# 7_High_Voltage.net
KiCad netlist of a schematic drawn in Altium Designer
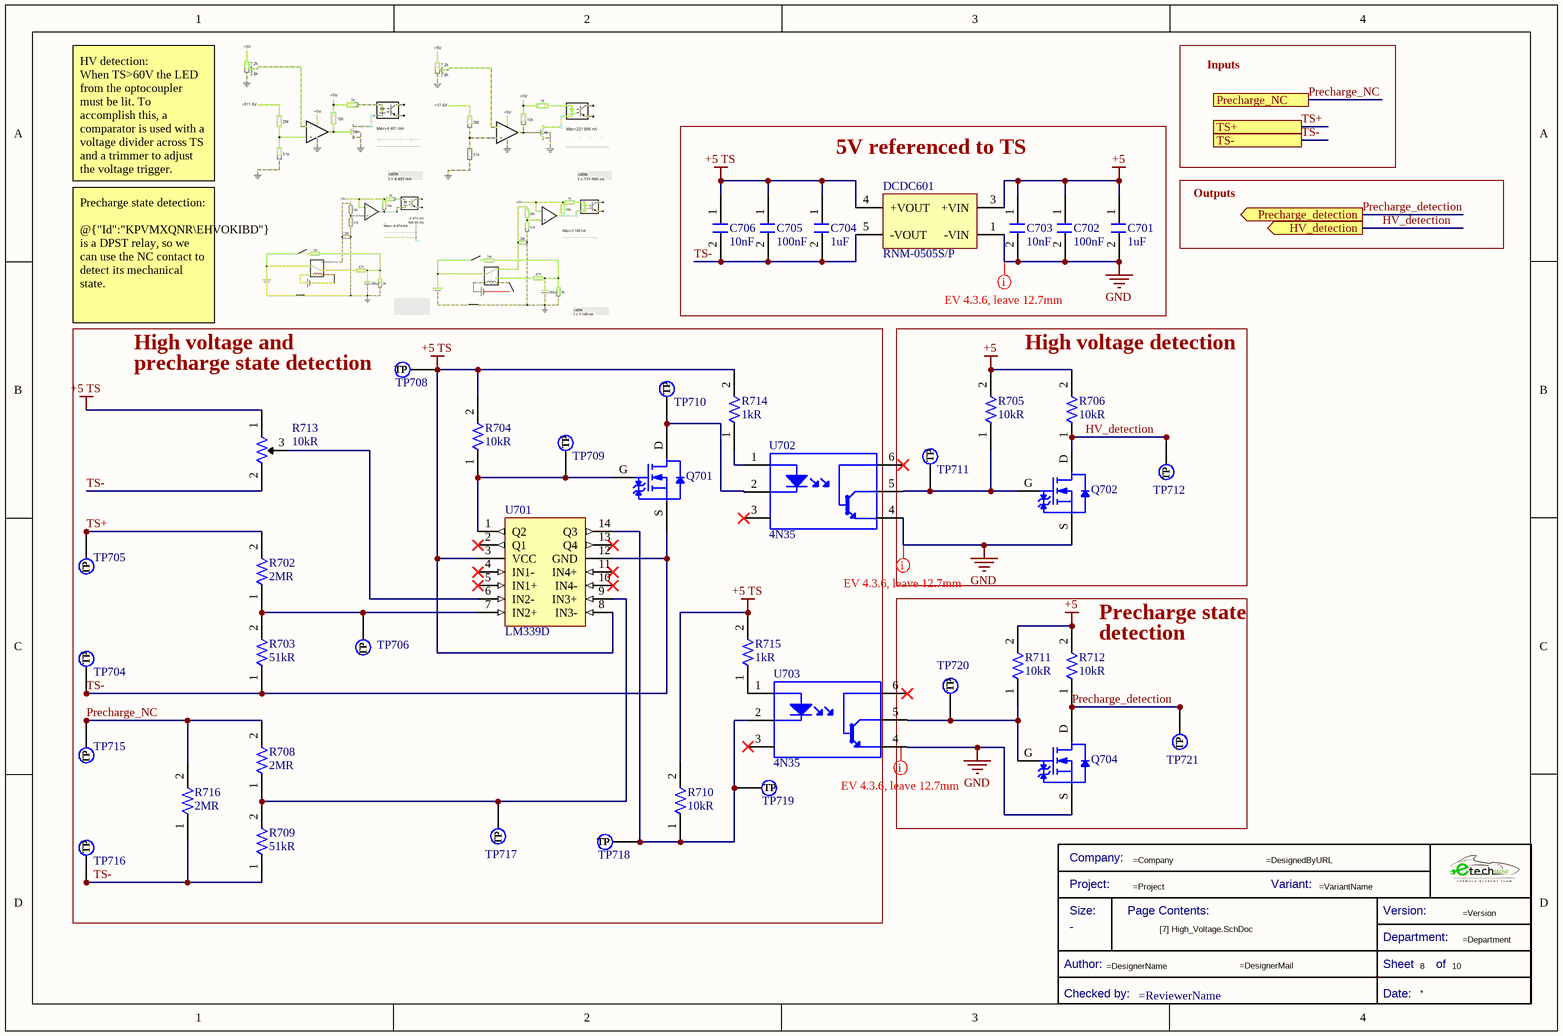
[diagram p0: [7] High_Voltage.SchDoc]

(export (version "E")
  (design (tool "Eeschema 10.0.6"))
  (components
    (comp (ref "*")
      (value "Title Block_template")
      (description "Standard Title Block")
      (fields (field (name "SIZE") "-"))
      (libsource (lib "e-Tech_Racing") (part "Title Block_template"))
    )
    (comp (ref "C701")
      (value "885012207103")
      (footprint "C0805FNPC-R")
      (fields
        (field (name "TOLERANCE") "10%")
        (field (name "CAPACITANCE") "1uF")
        (field (name ".CREATOR") "GP")
      )
      (libsource (lib "Passives") (part "C1u-50V-0805FNPC-X7R"))
    )
    (comp (ref "C702")
      (value "885012207098")
      (footprint "C0805FNPC-R")
      (description "Cap, 0.1ΜF, 50V, 10%, X7R, 0805")
      (fields
        (field (name "TOLERANCE") "10%")
        (field (name "CAPACITANCE") "100nF")
        (field (name ".CREATOR") "DR")
      )
      (libsource (lib "Passives") (part "C100n-50V-0805FNPC-X7R"))
    )
    (comp (ref "C703")
      (value "885012207092")
      (footprint "C0805FNPC-R")
      (description "Cap, 0.01ΜF, 50V, 10%, X7R, 0805")
      (fields
        (field (name "TOLERANCE") "10%")
        (field (name "CAPACITANCE") "10nF")
        (field (name ".CREATOR") "DR")
      )
      (libsource (lib "Passives") (part "C10n-50V-0805FNPC-X7R"))
    )
    (comp (ref "C704")
      (value "885012207103")
      (footprint "C0805FNPC-R")
      (fields
        (field (name "TOLERANCE") "10%")
        (field (name "CAPACITANCE") "1uF")
        (field (name ".CREATOR") "GP")
      )
      (libsource (lib "Passives") (part "C1u-50V-0805FNPC-X7R"))
    )
    (comp (ref "C705")
      (value "885012207098")
      (footprint "C0805FNPC-R")
      (description "Cap, 0.1ΜF, 50V, 10%, X7R, 0805")
      (fields
        (field (name "TOLERANCE") "10%")
        (field (name "CAPACITANCE") "100nF")
        (field (name ".CREATOR") "DR")
      )
      (libsource (lib "Passives") (part "C100n-50V-0805FNPC-X7R"))
    )
    (comp (ref "C706")
      (value "885012207092")
      (footprint "C0805FNPC-R")
      (description "Cap, 0.01ΜF, 50V, 10%, X7R, 0805")
      (fields
        (field (name "TOLERANCE") "10%")
        (field (name "CAPACITANCE") "10nF")
        (field (name ".CREATOR") "DR")
      )
      (libsource (lib "Passives") (part "C10n-50V-0805FNPC-X7R"))
    )
    (comp (ref "DCDC601")
      (value "RNM-0505S/P")
      (footprint "DCDC_RNM-0505S/P")
      (description "1W DC/DC-Converter 'ECONOLINE' DIP6 1kV unreg; V. In: 05; V. Out: 05; mA. Out: 200")
      (fields
        (field (name "MANUFACTURER") "Recom")
        (field (name "MANUFACTURER PART NUMBER") "RNM-0505S/P")
        (field (name ".CREATOR") "GP")
      )
      (libsource (lib "Semiconductor") (part "DCDC_RNM-0505S/P"))
    )
    (comp (ref "Q701")
      (value "SQ2318BES-T1_GE3")
      (footprint "TRT-NCH-3/35-CPH")
      (description "Automotive N-channel 40 V (d-s) 175C Mosfet SOT-23")
      (fields (field (name ".CREATOR") "DO"))
      (libsource (lib "Semiconductor") (part "TRT-NCH-8/40-SQ"))
    )
    (comp (ref "Q702")
      (value "SQ2318BES-T1_GE3")
      (footprint "TRT-NCH-3/35-CPH")
      (description "Automotive N-channel 40 V (d-s) 175C Mosfet SOT-23")
      (fields (field (name ".CREATOR") "DO"))
      (libsource (lib "Semiconductor") (part "TRT-NCH-8/40-SQ"))
    )
    (comp (ref "Q704")
      (value "SQ2318BES-T1_GE3")
      (footprint "TRT-NCH-3/35-CPH")
      (description "Automotive N-channel 40 V (d-s) 175C Mosfet SOT-23")
      (fields (field (name ".CREATOR") "DO"))
      (libsource (lib "Semiconductor") (part "TRT-NCH-8/40-SQ"))
    )
    (comp (ref "R702")
      (value "R2M-2512FTK")
      (footprint "R2512FTK")
      (description "Current Sense Resistors - SMD 3watts .002ohms 1%")
      (fields
        (field (name "MANUFACTURER") "Vishay Dale")
        (field (name "MANUFACTURER PART NUMBER") "WSLP25122L000FEA")
        (field (name "RESISTANCE") "2MR")
      )
      (libsource (lib "Passives") (part "R2M-2512FTK"))
    )
    (comp (ref "R703")
      (value "CRCW120610K0FKEA")
      (footprint "R1206FTK-W")
      (description "Res Thick Film 1206 51K Ohm 1% 1/4W ±100ppm/°C Molded SMD SMD Punched Carrier T/R")
      (fields
        (field (name "MANUFACTURER") "Panasonic")
        (field (name "MANUFACTURER PART NUMBER") "ERJ-S08F5102V")
        (field (name "RESISTANCE") "51kR")
        (field (name ".CREATOR") "DO")
      )
      (libsource (lib "Passives") (part "R51k-1206FTK"))
    )
    (comp (ref "R704")
      (value "CR0805-JW-103ELF")
      (footprint "R0805FTK")
      (fields
        (field (name "TOLERANCE") "5%")
        (field (name "RESISTANCE") "10kR")
        (field (name ".CREATOR") "DR")
      )
      (libsource (lib "Passives") (part "R10k-0805FTK"))
    )
    (comp (ref "R705")
      (value "CR0805-JW-103ELF")
      (footprint "R0805FTK")
      (fields
        (field (name "TOLERANCE") "5%")
        (field (name "RESISTANCE") "10kR")
        (field (name ".CREATOR") "DR")
      )
      (libsource (lib "Passives") (part "R10k-0805FTK"))
    )
    (comp (ref "R706")
      (value "CR0805-JW-103ELF")
      (footprint "R0805FTK")
      (fields
        (field (name "TOLERANCE") "5%")
        (field (name "RESISTANCE") "10kR")
        (field (name ".CREATOR") "DR")
      )
      (libsource (lib "Passives") (part "R10k-0805FTK"))
    )
    (comp (ref "R708")
      (value "R2M-2512FTK")
      (footprint "R2512FTK")
      (description "Current Sense Resistors - SMD 3watts .002ohms 1%")
      (fields
        (field (name "MANUFACTURER") "Vishay Dale")
        (field (name "MANUFACTURER PART NUMBER") "WSLP25122L000FEA")
        (field (name "RESISTANCE") "2MR")
      )
      (libsource (lib "Passives") (part "R2M-2512FTK"))
    )
    (comp (ref "R709")
      (value "CRCW120610K0FKEA")
      (footprint "R1206FTK-W")
      (description "Res Thick Film 1206 51K Ohm 1% 1/4W ±100ppm/°C Molded SMD SMD Punched Carrier T/R")
      (fields
        (field (name "MANUFACTURER") "Panasonic")
        (field (name "MANUFACTURER PART NUMBER") "ERJ-S08F5102V")
        (field (name "RESISTANCE") "51kR")
        (field (name ".CREATOR") "DO")
      )
      (libsource (lib "Passives") (part "R51k-1206FTK"))
    )
    (comp (ref "R710")
      (value "CR0805-JW-103ELF")
      (footprint "R0805FTK")
      (fields
        (field (name "TOLERANCE") "5%")
        (field (name "RESISTANCE") "10kR")
        (field (name ".CREATOR") "DR")
      )
      (libsource (lib "Passives") (part "R10k-0805FTK"))
    )
    (comp (ref "R711")
      (value "CR0805-JW-103ELF")
      (footprint "R0805FTK")
      (fields
        (field (name "TOLERANCE") "5%")
        (field (name "RESISTANCE") "10kR")
        (field (name ".CREATOR") "DR")
      )
      (libsource (lib "Passives") (part "R10k-0805FTK"))
    )
    (comp (ref "R712")
      (value "CR0805-JW-103ELF")
      (footprint "R0805FTK")
      (fields
        (field (name "TOLERANCE") "5%")
        (field (name "RESISTANCE") "10kR")
        (field (name ".CREATOR") "DR")
      )
      (libsource (lib "Passives") (part "R10k-0805FTK"))
    )
    (comp (ref "R713")
      (value "3296W-1-103LF")
      (footprint "R10k-VTR")
      (description "Trimmer, Cermet, Rest 10 Kilohms, PCB, 25 Turns, Pwr-Rtg 0.5W, 3296 Series")
      (fields
        (field (name "MANUFACTURER") "Bourns")
        (field (name "TOLERANCE") "10%")
        (field (name "RESISTANCE") "10kR")
        (field (name ".CREATOR") "DO")
      )
      (libsource (lib "Passives") (part "R10k-VTR"))
    )
    (comp (ref "R714")
      (value "CR0805-JW-102ELF")
      (footprint "R0805FTK")
      (description "Res Thick Film 0805 1K Ohm 5% 1/8W ±200ppm/°C Molded SMD SMD Paper Tape on Plastic Reel")
      (fields
        (field (name "TOLERANCE") "5%")
        (field (name "RESISTANCE") "1kR")
        (field (name ".CREATOR") "GP")
      )
      (libsource (lib "Passives") (part "R1k-0805FTK"))
    )
    (comp (ref "R715")
      (value "CR0805-JW-102ELF")
      (footprint "R0805FTK")
      (description "Res Thick Film 0805 1K Ohm 5% 1/8W ±200ppm/°C Molded SMD SMD Paper Tape on Plastic Reel")
      (fields
        (field (name "TOLERANCE") "5%")
        (field (name "RESISTANCE") "1kR")
        (field (name ".CREATOR") "GP")
      )
      (libsource (lib "Passives") (part "R1k-0805FTK"))
    )
    (comp (ref "R716")
      (value "R2M-2512FTK")
      (footprint "R2512FTK")
      (description "Current Sense Resistors - SMD 3watts .002ohms 1%")
      (fields
        (field (name "MANUFACTURER") "Vishay Dale")
        (field (name "MANUFACTURER PART NUMBER") "WSLP25122L000FEA")
        (field (name "RESISTANCE") "2MR")
      )
      (libsource (lib "Passives") (part "R2M-2512FTK"))
    )
    (comp (ref "TP704")
      (value "TestPoint")
      (footprint "TestPoint")
      (description "Test Point 1x1 mm")
      (fields (field (name ".CREATOR") "GP") (field (name ".PCBCHECK") "GP") (field (name ".SCHCHECK") "GP"))
      (libsource (lib "e-Tech_Racing") (part "TestPoint"))
    )
    (comp (ref "TP705")
      (value "TestPoint")
      (footprint "TestPoint")
      (description "Test Point 1x1 mm")
      (fields (field (name ".CREATOR") "GP") (field (name ".PCBCHECK") "GP") (field (name ".SCHCHECK") "GP"))
      (libsource (lib "e-Tech_Racing") (part "TestPoint"))
    )
    (comp (ref "TP706")
      (value "TestPoint")
      (footprint "TestPoint")
      (description "Test Point 1x1 mm")
      (fields (field (name ".CREATOR") "GP") (field (name ".PCBCHECK") "GP") (field (name ".SCHCHECK") "GP"))
      (libsource (lib "e-Tech_Racing") (part "TestPoint"))
    )
    (comp (ref "TP708")
      (value "TestPoint")
      (footprint "TestPoint")
      (description "Test Point 1x1 mm")
      (fields (field (name ".CREATOR") "GP") (field (name ".PCBCHECK") "GP") (field (name ".SCHCHECK") "GP"))
      (libsource (lib "e-Tech_Racing") (part "TestPoint"))
    )
    (comp (ref "TP709")
      (value "TestPoint")
      (footprint "TestPoint")
      (description "Test Point 1x1 mm")
      (fields (field (name ".CREATOR") "GP") (field (name ".PCBCHECK") "GP") (field (name ".SCHCHECK") "GP"))
      (libsource (lib "e-Tech_Racing") (part "TestPoint"))
    )
    (comp (ref "TP710")
      (value "TestPoint")
      (footprint "TestPoint")
      (description "Test Point 1x1 mm")
      (fields (field (name ".CREATOR") "GP") (field (name ".PCBCHECK") "GP") (field (name ".SCHCHECK") "GP"))
      (libsource (lib "e-Tech_Racing") (part "TestPoint"))
    )
    (comp (ref "TP711")
      (value "TestPoint")
      (footprint "TestPoint")
      (description "Test Point 1x1 mm")
      (fields (field (name ".CREATOR") "GP") (field (name ".PCBCHECK") "GP") (field (name ".SCHCHECK") "GP"))
      (libsource (lib "e-Tech_Racing") (part "TestPoint"))
    )
    (comp (ref "TP712")
      (value "TestPoint")
      (footprint "TestPoint")
      (description "Test Point 1x1 mm")
      (fields (field (name ".CREATOR") "GP") (field (name ".PCBCHECK") "GP") (field (name ".SCHCHECK") "GP"))
      (libsource (lib "e-Tech_Racing") (part "TestPoint"))
    )
    (comp (ref "TP715")
      (value "TestPoint")
      (footprint "TestPoint")
      (description "Test Point 1x1 mm")
      (fields (field (name ".CREATOR") "GP") (field (name ".PCBCHECK") "GP") (field (name ".SCHCHECK") "GP"))
      (libsource (lib "e-Tech_Racing") (part "TestPoint"))
    )
    (comp (ref "TP716")
      (value "TestPoint")
      (footprint "TestPoint")
      (description "Test Point 1x1 mm")
      (fields (field (name ".CREATOR") "GP") (field (name ".PCBCHECK") "GP") (field (name ".SCHCHECK") "GP"))
      (libsource (lib "e-Tech_Racing") (part "TestPoint"))
    )
    (comp (ref "TP717")
      (value "TestPoint")
      (footprint "TestPoint")
      (description "Test Point 1x1 mm")
      (fields (field (name ".CREATOR") "GP") (field (name ".PCBCHECK") "GP") (field (name ".SCHCHECK") "GP"))
      (libsource (lib "e-Tech_Racing") (part "TestPoint"))
    )
    (comp (ref "TP718")
      (value "TestPoint")
      (footprint "TestPoint")
      (description "Test Point 1x1 mm")
      (fields (field (name ".CREATOR") "GP") (field (name ".PCBCHECK") "GP") (field (name ".SCHCHECK") "GP"))
      (libsource (lib "e-Tech_Racing") (part "TestPoint"))
    )
    (comp (ref "TP719")
      (value "TestPoint")
      (footprint "TestPoint")
      (description "Test Point 1x1 mm")
      (fields (field (name ".CREATOR") "GP") (field (name ".PCBCHECK") "GP") (field (name ".SCHCHECK") "GP"))
      (libsource (lib "e-Tech_Racing") (part "TestPoint"))
    )
    (comp (ref "TP720")
      (value "TestPoint")
      (footprint "TestPoint")
      (description "Test Point 1x1 mm")
      (fields (field (name ".CREATOR") "GP") (field (name ".PCBCHECK") "GP") (field (name ".SCHCHECK") "GP"))
      (libsource (lib "e-Tech_Racing") (part "TestPoint"))
    )
    (comp (ref "TP721")
      (value "TestPoint")
      (footprint "TestPoint")
      (description "Test Point 1x1 mm")
      (fields (field (name ".CREATOR") "GP") (field (name ".PCBCHECK") "GP") (field (name ".SCHCHECK") "GP"))
      (libsource (lib "e-Tech_Racing") (part "TestPoint"))
    )
    (comp (ref "U701")
      (value "LM339D")
      (footprint "Array_4_Amp_LM339D")
      (description "Comparator Quad ±18V/36V 14-Pin SOIC Tube")
      (fields
        (field (name "MANUFACTURER") "Texas Instruments")
        (field (name "MANUFACTURER PART NUMBER") "LM339D")
        (field (name ".CREATOR") "DO")
      )
      (libsource (lib "Integrated circuits") (part "Array_4_Amp_LM339D"))
    )
    (comp (ref "U702")
      (value "4N35")
      (footprint "Optocoupler_4N35")
      (description "Optocoupler DC-IN 1-CH Transistor With Base DC-OUT 6-Pin PDIP SMD T/R")
      (fields
        (field (name "MANUFACTURER") "Vishay Lite-On")
        (field (name "MANUFACTURER PART NUMBER") "CNY17-4S-TA1")
        (field (name ".CREATOR") "DO")
      )
      (libsource (lib "Semiconductor") (part "Optocoupler_4N35"))
    )
    (comp (ref "U703")
      (value "4N35")
      (footprint "Optocoupler_4N35")
      (description "Optocoupler DC-IN 1-CH Transistor With Base DC-OUT 6-Pin PDIP SMD T/R")
      (fields
        (field (name "MANUFACTURER") "Vishay Lite-On")
        (field (name "MANUFACTURER PART NUMBER") "CNY17-4S-TA1")
        (field (name ".CREATOR") "DO")
      )
      (libsource (lib "Semiconductor") (part "Optocoupler_4N35"))
    )
  )
  (nets
    (net (code "1") (name "+5") (class "Default")
      (node (ref "C701") (pin "1") (pinfunction "1_1") (pintype "passive"))
      (node (ref "C702") (pin "1") (pinfunction "1_1") (pintype "passive"))
      (node (ref "C703") (pin "1") (pinfunction "1_1") (pintype "passive"))
      (node (ref "DCDC601") (pin "3") (pinfunction "+VIN_3") (pintype "passive"))
      (node (ref "R705") (pin "2") (pinfunction "2_2") (pintype "passive"))
      (node (ref "R706") (pin "2") (pinfunction "2_2") (pintype "passive"))
      (node (ref "R711") (pin "2") (pinfunction "2_2") (pintype "passive"))
      (node (ref "R712") (pin "2") (pinfunction "2_2") (pintype "passive"))
    )
    (net (code "2") (name "+5 TS") (class "Default")
      (node (ref "C704") (pin "1") (pinfunction "1_1") (pintype "passive"))
      (node (ref "C705") (pin "1") (pinfunction "1_1") (pintype "passive"))
      (node (ref "C706") (pin "1") (pinfunction "1_1") (pintype "passive"))
      (node (ref "DCDC601") (pin "4") (pinfunction "+VOUT_4") (pintype "passive"))
      (node (ref "R704") (pin "2") (pinfunction "2_2") (pintype "passive"))
      (node (ref "R710") (pin "2") (pinfunction "2_2") (pintype "passive"))
      (node (ref "R713") (pin "1") (pinfunction "2_1") (pintype "passive"))
      (node (ref "R714") (pin "2") (pinfunction "2_2") (pintype "passive"))
      (node (ref "R715") (pin "2") (pinfunction "2_2") (pintype "passive"))
      (node (ref "TP708") (pin "1") (pinfunction "TP_1") (pintype "passive"))
      (node (ref "U701") (pin "3") (pinfunction "VCC_3") (pintype "power_in"))
      (node (ref "U701") (pin "8") (pinfunction "IN3-_8") (pintype "input"))
    )
    (net (code "3") (name "/HV_detection") (class "Default")
      (node (ref "Q702") (pin "D") (pinfunction "D_D") (pintype "passive"))
      (node (ref "R706") (pin "1") (pinfunction "1_1") (pintype "passive"))
      (node (ref "TP712") (pin "1") (pinfunction "TP_1") (pintype "passive"))
    )
    (net (code "4") (name "/Precharge_NC") (class "Default")
      (node (ref "R708") (pin "2") (pinfunction "2_2") (pintype "passive"))
      (node (ref "R716") (pin "2") (pinfunction "2_2") (pintype "passive"))
      (node (ref "TP715") (pin "1") (pinfunction "TP_1") (pintype "passive"))
    )
    (net (code "5") (name "/Precharge_detection") (class "Default")
      (node (ref "Q704") (pin "D") (pinfunction "D_D") (pintype "passive"))
      (node (ref "R712") (pin "1") (pinfunction "1_1") (pintype "passive"))
      (node (ref "TP721") (pin "1") (pinfunction "TP_1") (pintype "passive"))
    )
    (net (code "6") (name "/TS+") (class "Default")
      (node (ref "R702") (pin "2") (pinfunction "2_2") (pintype "passive"))
      (node (ref "TP705") (pin "1") (pinfunction "TP_1") (pintype "passive"))
    )
    (net (code "7") (name "/TS-") (class "Default")
      (node (ref "C704") (pin "2") (pinfunction "2_2") (pintype "passive"))
      (node (ref "C705") (pin "2") (pinfunction "2_2") (pintype "passive"))
      (node (ref "C706") (pin "2") (pinfunction "2_2") (pintype "passive"))
      (node (ref "DCDC601") (pin "5") (pinfunction "-VOUT_5") (pintype "passive"))
      (node (ref "Q701") (pin "S") (pinfunction "S_S") (pintype "passive"))
      (node (ref "R703") (pin "1") (pinfunction "1_1") (pintype "passive"))
      (node (ref "R709") (pin "1") (pinfunction "1_1") (pintype "passive"))
      (node (ref "R713") (pin "2") (pinfunction "2_2") (pintype "passive"))
      (node (ref "R716") (pin "1") (pinfunction "1_1") (pintype "passive"))
      (node (ref "TP704") (pin "1") (pinfunction "TP_1") (pintype "passive"))
      (node (ref "TP716") (pin "1") (pinfunction "TP_1") (pintype "passive"))
      (node (ref "U701") (pin "12") (pinfunction "GND_12") (pintype "power_in"))
    )
    (net (code "8") (name "GND") (class "Default")
      (node (ref "C701") (pin "2") (pinfunction "2_2") (pintype "passive"))
      (node (ref "C702") (pin "2") (pinfunction "2_2") (pintype "passive"))
      (node (ref "C703") (pin "2") (pinfunction "2_2") (pintype "passive"))
      (node (ref "DCDC601") (pin "1") (pinfunction "-VIN_1") (pintype "passive"))
      (node (ref "Q702") (pin "S") (pinfunction "S_S") (pintype "passive"))
      (node (ref "Q704") (pin "S") (pinfunction "S_S") (pintype "passive"))
      (node (ref "U702") (pin "4") (pinfunction "E_4") (pintype "passive"))
      (node (ref "U703") (pin "4") (pinfunction "E_4") (pintype "passive"))
    )
    (net (code "9") (name "Net-(TP706-TP)") (class "Default")
      (node (ref "R702") (pin "1") (pinfunction "1_1") (pintype "passive"))
      (node (ref "R703") (pin "2") (pinfunction "2_2") (pintype "passive"))
      (node (ref "TP706") (pin "1") (pinfunction "TP_1") (pintype "passive"))
      (node (ref "U701") (pin "7") (pinfunction "IN2+_7") (pintype "input"))
    )
    (net (code "10") (name "Net-(TP709-TP)") (class "Default")
      (node (ref "Q701") (pin "G") (pinfunction "G_G") (pintype "passive"))
      (node (ref "R704") (pin "1") (pinfunction "1_1") (pintype "passive"))
      (node (ref "TP709") (pin "1") (pinfunction "TP_1") (pintype "passive"))
      (node (ref "U701") (pin "1") (pinfunction "Q2_1") (pintype "output"))
    )
    (net (code "11") (name "Net-(TP710-TP)") (class "Default")
      (node (ref "Q701") (pin "D") (pinfunction "D_D") (pintype "passive"))
      (node (ref "TP710") (pin "1") (pinfunction "TP_1") (pintype "passive"))
      (node (ref "U702") (pin "2") (pinfunction "K_2") (pintype "passive"))
    )
    (net (code "12") (name "Net-(TP711-TP)") (class "Default")
      (node (ref "Q702") (pin "G") (pinfunction "G_G") (pintype "passive"))
      (node (ref "R705") (pin "1") (pinfunction "1_1") (pintype "passive"))
      (node (ref "TP711") (pin "1") (pinfunction "TP_1") (pintype "passive"))
      (node (ref "U702") (pin "5") (pinfunction "E_5") (pintype "passive"))
    )
    (net (code "13") (name "Net-(TP717-TP)") (class "Default")
      (node (ref "R708") (pin "1") (pinfunction "1_1") (pintype "passive"))
      (node (ref "R709") (pin "2") (pinfunction "2_2") (pintype "passive"))
      (node (ref "TP717") (pin "1") (pinfunction "TP_1") (pintype "passive"))
      (node (ref "U701") (pin "9") (pinfunction "IN3+_9") (pintype "input"))
    )
    (net (code "14") (name "Net-(TP718-TP)") (class "Default")
      (node (ref "R710") (pin "1") (pinfunction "1_1") (pintype "passive"))
      (node (ref "TP718") (pin "1") (pinfunction "TP_1") (pintype "passive"))
      (node (ref "TP719") (pin "1") (pinfunction "TP_1") (pintype "passive"))
      (node (ref "U701") (pin "14") (pinfunction "Q3_14") (pintype "output"))
      (node (ref "U703") (pin "2") (pinfunction "K_2") (pintype "passive"))
    )
    (net (code "15") (name "Net-(TP720-TP)") (class "Default")
      (node (ref "Q704") (pin "G") (pinfunction "G_G") (pintype "passive"))
      (node (ref "R711") (pin "1") (pinfunction "1_1") (pintype "passive"))
      (node (ref "TP720") (pin "1") (pinfunction "TP_1") (pintype "passive"))
      (node (ref "U703") (pin "5") (pinfunction "E_5") (pintype "passive"))
    )
    (net (code "16") (name "Net-(U701-IN2-)") (class "Default")
      (node (ref "R713") (pin "3") (pinfunction "3_3") (pintype "passive"))
      (node (ref "U701") (pin "6") (pinfunction "IN2-_6") (pintype "input"))
    )
    (net (code "17") (name "Net-(U702-A)") (class "Default")
      (node (ref "R714") (pin "1") (pinfunction "1_1") (pintype "passive"))
      (node (ref "U702") (pin "1") (pinfunction "A_1") (pintype "passive"))
    )
    (net (code "18") (name "Net-(U703-A)") (class "Default")
      (node (ref "R715") (pin "1") (pinfunction "1_1") (pintype "passive"))
      (node (ref "U703") (pin "1") (pinfunction "A_1") (pintype "passive"))
    )
    (net (code "19") (name "unconnected-(U701-IN1+-Pad5)") (class "Default")
      (node (ref "U701") (pin "5") (pinfunction "IN1+_5") (pintype "input+no_connect"))
    )
    (net (code "20") (name "unconnected-(U701-IN1--Pad4)") (class "Default")
      (node (ref "U701") (pin "4") (pinfunction "IN1-_4") (pintype "input+no_connect"))
    )
    (net (code "21") (name "unconnected-(U701-IN4+-Pad11)") (class "Default")
      (node (ref "U701") (pin "11") (pinfunction "IN4+_11") (pintype "input+no_connect"))
    )
    (net (code "22") (name "unconnected-(U701-IN4--Pad10)") (class "Default")
      (node (ref "U701") (pin "10") (pinfunction "IN4-_10") (pintype "input+no_connect"))
    )
    (net (code "23") (name "unconnected-(U701-Q1-Pad2)") (class "Default")
      (node (ref "U701") (pin "2") (pinfunction "Q1_2") (pintype "output+no_connect"))
    )
    (net (code "24") (name "unconnected-(U701-Q4-Pad13)") (class "Default")
      (node (ref "U701") (pin "13") (pinfunction "Q4_13") (pintype "output+no_connect"))
    )
    (net (code "25") (name "unconnected-(U702-C-Pad3)") (class "Default")
      (node (ref "U702") (pin "3") (pinfunction "C_3") (pintype "passive+no_connect"))
    )
    (net (code "26") (name "unconnected-(U702-E-Pad6)") (class "Default")
      (node (ref "U702") (pin "6") (pinfunction "E_6") (pintype "passive+no_connect"))
    )
    (net (code "27") (name "unconnected-(U703-C-Pad3)") (class "Default")
      (node (ref "U703") (pin "3") (pinfunction "C_3") (pintype "passive+no_connect"))
    )
    (net (code "28") (name "unconnected-(U703-E-Pad6)") (class "Default")
      (node (ref "U703") (pin "6") (pinfunction "E_6") (pintype "passive+no_connect"))
    )
  )
)
